# samtec_to_dsub.net
KiCad netlist of a schematic drawn in EAGLE
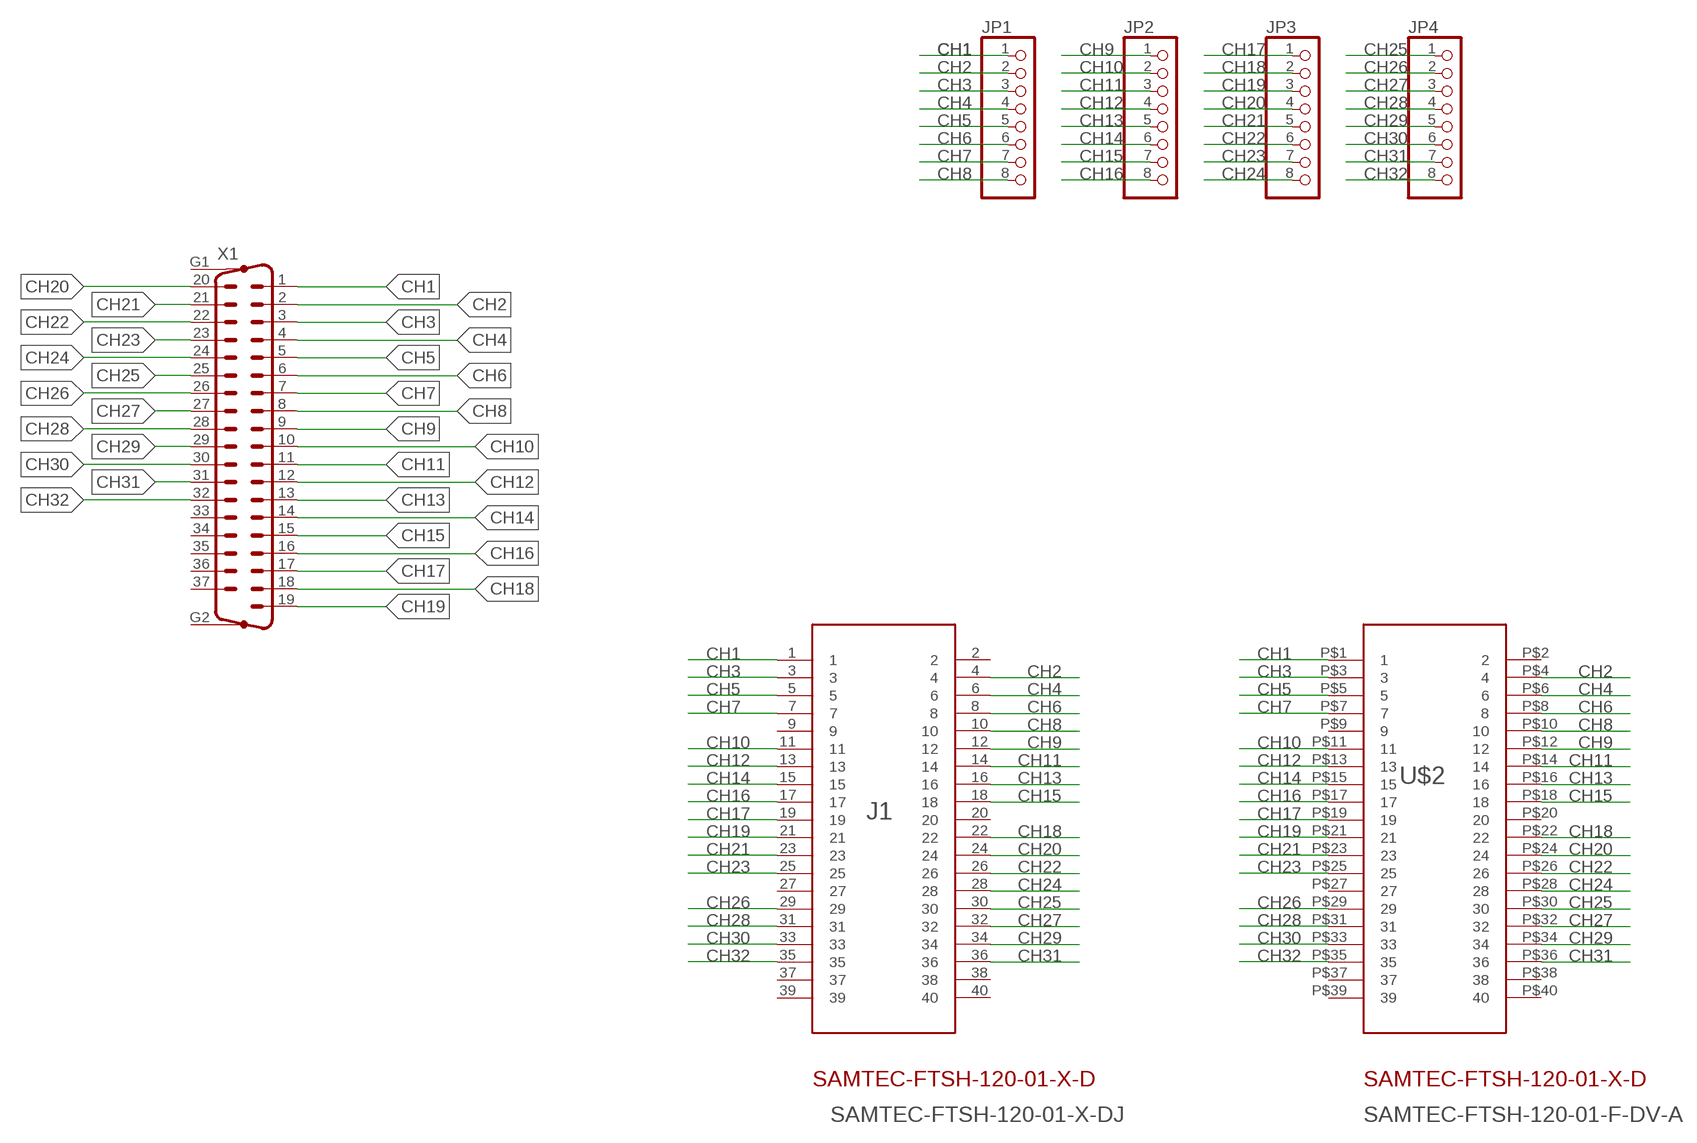
[diagram p0: schematic, sheet 1]

(export (version "E")
  (design (tool "Eeschema 10.0.6"))
  (components
    (comp (ref "J1")
      (value "SAMTEC-FTSH-120-01-X-DJ")
      (footprint "eagle-import:SAMTEC-FTSH-120-01-X-D")
      (libsource (lib "eagle-import") (part "SAMTEC-FTSH-120-01-X-DJ"))
    )
    (comp (ref "JP1")
      (value "PINHD-1X8")
      (footprint "eagle-import:1X08")
      (libsource (lib "eagle-import") (part "PINHD-1X8"))
    )
    (comp (ref "JP2")
      (value "PINHD-1X8")
      (footprint "eagle-import:1X08")
      (libsource (lib "eagle-import") (part "PINHD-1X8"))
    )
    (comp (ref "JP3")
      (value "PINHD-1X8")
      (footprint "eagle-import:1X08")
      (libsource (lib "eagle-import") (part "PINHD-1X8"))
    )
    (comp (ref "JP4")
      (value "PINHD-1X8")
      (footprint "eagle-import:1X08")
      (libsource (lib "eagle-import") (part "PINHD-1X8"))
    )
    (comp (ref "U$2")
      (value "SAMTEC-FTSH-120-01-F-DV-A")
      (footprint "eagle-import:SAMTEC-FTSH-LARGEPAD")
      (libsource (lib "eagle-import") (part "SAMTEC-FTSH-120-01-F-DV-A"))
    )
    (comp (ref "X1")
      (value "M37HP")
      (footprint "eagle-import:M37HP")
      (libsource (lib "eagle-import") (part "M37HP"))
    )
  )
  (nets
    (net (code "1") (name "CH1") (class "Default")
      (node (ref "J1") (pin "1") (pinfunction "1_1") (pintype "passive"))
      (node (ref "JP1") (pin "1") (pinfunction "1_1") (pintype "passive"))
      (node (ref "U$2") (pin "P$1") (pinfunction "1_P$1") (pintype "passive"))
      (node (ref "X1") (pin "1") (pinfunction "1_1") (pintype "passive"))
    )
    (net (code "2") (name "CH2") (class "Default")
      (node (ref "J1") (pin "4") (pinfunction "4_4") (pintype "passive"))
      (node (ref "JP1") (pin "2") (pinfunction "2_2") (pintype "passive"))
      (node (ref "U$2") (pin "P$4") (pinfunction "4_P$4") (pintype "passive"))
      (node (ref "X1") (pin "2") (pinfunction "2_2") (pintype "passive"))
    )
    (net (code "3") (name "CH3") (class "Default")
      (node (ref "J1") (pin "3") (pinfunction "3_3") (pintype "passive"))
      (node (ref "JP1") (pin "3") (pinfunction "3_3") (pintype "passive"))
      (node (ref "U$2") (pin "P$3") (pinfunction "3_P$3") (pintype "passive"))
      (node (ref "X1") (pin "3") (pinfunction "3_3") (pintype "passive"))
    )
    (net (code "4") (name "CH4") (class "Default")
      (node (ref "J1") (pin "6") (pinfunction "6_6") (pintype "passive"))
      (node (ref "JP1") (pin "4") (pinfunction "4_4") (pintype "passive"))
      (node (ref "U$2") (pin "P$6") (pinfunction "6_P$6") (pintype "passive"))
      (node (ref "X1") (pin "4") (pinfunction "4_4") (pintype "passive"))
    )
    (net (code "5") (name "CH5") (class "Default")
      (node (ref "J1") (pin "5") (pinfunction "5_5") (pintype "passive"))
      (node (ref "JP1") (pin "5") (pinfunction "5_5") (pintype "passive"))
      (node (ref "U$2") (pin "P$5") (pinfunction "5_P$5") (pintype "passive"))
      (node (ref "X1") (pin "5") (pinfunction "5_5") (pintype "passive"))
    )
    (net (code "6") (name "CH6") (class "Default")
      (node (ref "J1") (pin "8") (pinfunction "8_8") (pintype "passive"))
      (node (ref "JP1") (pin "6") (pinfunction "6_6") (pintype "passive"))
      (node (ref "U$2") (pin "P$8") (pinfunction "8_P$8") (pintype "passive"))
      (node (ref "X1") (pin "6") (pinfunction "6_6") (pintype "passive"))
    )
    (net (code "7") (name "CH7") (class "Default")
      (node (ref "J1") (pin "7") (pinfunction "7_7") (pintype "passive"))
      (node (ref "JP1") (pin "7") (pinfunction "7_7") (pintype "passive"))
      (node (ref "U$2") (pin "P$7") (pinfunction "7_P$7") (pintype "passive"))
      (node (ref "X1") (pin "7") (pinfunction "7_7") (pintype "passive"))
    )
    (net (code "8") (name "CH8") (class "Default")
      (node (ref "J1") (pin "10") (pinfunction "10_10") (pintype "passive"))
      (node (ref "JP1") (pin "8") (pinfunction "8_8") (pintype "passive"))
      (node (ref "U$2") (pin "P$10") (pinfunction "10_P$10") (pintype "passive"))
      (node (ref "X1") (pin "8") (pinfunction "8_8") (pintype "passive"))
    )
    (net (code "9") (name "CH9") (class "Default")
      (node (ref "J1") (pin "12") (pinfunction "12_12") (pintype "passive"))
      (node (ref "JP2") (pin "1") (pinfunction "1_1") (pintype "passive"))
      (node (ref "U$2") (pin "P$12") (pinfunction "12_P$12") (pintype "passive"))
      (node (ref "X1") (pin "9") (pinfunction "9_9") (pintype "passive"))
    )
    (net (code "10") (name "CH10") (class "Default")
      (node (ref "J1") (pin "11") (pinfunction "11_11") (pintype "passive"))
      (node (ref "JP2") (pin "2") (pinfunction "2_2") (pintype "passive"))
      (node (ref "U$2") (pin "P$11") (pinfunction "11_P$11") (pintype "passive"))
      (node (ref "X1") (pin "10") (pinfunction "10_10") (pintype "passive"))
    )
    (net (code "11") (name "CH11") (class "Default")
      (node (ref "J1") (pin "14") (pinfunction "14_14") (pintype "passive"))
      (node (ref "JP2") (pin "3") (pinfunction "3_3") (pintype "passive"))
      (node (ref "U$2") (pin "P$14") (pinfunction "14_P$14") (pintype "passive"))
      (node (ref "X1") (pin "11") (pinfunction "11_11") (pintype "passive"))
    )
    (net (code "12") (name "CH12") (class "Default")
      (node (ref "J1") (pin "13") (pinfunction "13_13") (pintype "passive"))
      (node (ref "JP2") (pin "4") (pinfunction "4_4") (pintype "passive"))
      (node (ref "U$2") (pin "P$13") (pinfunction "13_P$13") (pintype "passive"))
      (node (ref "X1") (pin "12") (pinfunction "12_12") (pintype "passive"))
    )
    (net (code "13") (name "CH13") (class "Default")
      (node (ref "J1") (pin "16") (pinfunction "16_16") (pintype "passive"))
      (node (ref "JP2") (pin "5") (pinfunction "5_5") (pintype "passive"))
      (node (ref "U$2") (pin "P$16") (pinfunction "16_P$16") (pintype "passive"))
      (node (ref "X1") (pin "13") (pinfunction "13_13") (pintype "passive"))
    )
    (net (code "14") (name "CH14") (class "Default")
      (node (ref "J1") (pin "15") (pinfunction "15_15") (pintype "passive"))
      (node (ref "JP2") (pin "6") (pinfunction "6_6") (pintype "passive"))
      (node (ref "U$2") (pin "P$15") (pinfunction "15_P$15") (pintype "passive"))
      (node (ref "X1") (pin "14") (pinfunction "14_14") (pintype "passive"))
    )
    (net (code "15") (name "CH15") (class "Default")
      (node (ref "J1") (pin "18") (pinfunction "18_18") (pintype "passive"))
      (node (ref "JP2") (pin "7") (pinfunction "7_7") (pintype "passive"))
      (node (ref "U$2") (pin "P$18") (pinfunction "18_P$18") (pintype "passive"))
      (node (ref "X1") (pin "15") (pinfunction "15_15") (pintype "passive"))
    )
    (net (code "16") (name "CH16") (class "Default")
      (node (ref "J1") (pin "17") (pinfunction "17_17") (pintype "passive"))
      (node (ref "JP2") (pin "8") (pinfunction "8_8") (pintype "passive"))
      (node (ref "U$2") (pin "P$17") (pinfunction "17_P$17") (pintype "passive"))
      (node (ref "X1") (pin "16") (pinfunction "16_16") (pintype "passive"))
    )
    (net (code "17") (name "CH17") (class "Default")
      (node (ref "J1") (pin "19") (pinfunction "19_19") (pintype "passive"))
      (node (ref "JP3") (pin "1") (pinfunction "1_1") (pintype "passive"))
      (node (ref "U$2") (pin "P$19") (pinfunction "19_P$19") (pintype "passive"))
      (node (ref "X1") (pin "17") (pinfunction "17_17") (pintype "passive"))
    )
    (net (code "18") (name "CH18") (class "Default")
      (node (ref "J1") (pin "22") (pinfunction "22_22") (pintype "passive"))
      (node (ref "JP3") (pin "2") (pinfunction "2_2") (pintype "passive"))
      (node (ref "U$2") (pin "P$22") (pinfunction "22_P$22") (pintype "passive"))
      (node (ref "X1") (pin "18") (pinfunction "18_18") (pintype "passive"))
    )
    (net (code "19") (name "CH19") (class "Default")
      (node (ref "J1") (pin "21") (pinfunction "21_21") (pintype "passive"))
      (node (ref "JP3") (pin "3") (pinfunction "3_3") (pintype "passive"))
      (node (ref "U$2") (pin "P$21") (pinfunction "21_P$21") (pintype "passive"))
      (node (ref "X1") (pin "19") (pinfunction "19_19") (pintype "passive"))
    )
    (net (code "20") (name "CH20") (class "Default")
      (node (ref "J1") (pin "24") (pinfunction "24_24") (pintype "passive"))
      (node (ref "JP3") (pin "4") (pinfunction "4_4") (pintype "passive"))
      (node (ref "U$2") (pin "P$24") (pinfunction "24_P$24") (pintype "passive"))
      (node (ref "X1") (pin "20") (pinfunction "20_20") (pintype "passive"))
    )
    (net (code "21") (name "CH21") (class "Default")
      (node (ref "J1") (pin "23") (pinfunction "23_23") (pintype "passive"))
      (node (ref "JP3") (pin "5") (pinfunction "5_5") (pintype "passive"))
      (node (ref "U$2") (pin "P$23") (pinfunction "23_P$23") (pintype "passive"))
      (node (ref "X1") (pin "21") (pinfunction "21_21") (pintype "passive"))
    )
    (net (code "22") (name "CH22") (class "Default")
      (node (ref "J1") (pin "26") (pinfunction "26_26") (pintype "passive"))
      (node (ref "JP3") (pin "6") (pinfunction "6_6") (pintype "passive"))
      (node (ref "U$2") (pin "P$26") (pinfunction "26_P$26") (pintype "passive"))
      (node (ref "X1") (pin "22") (pinfunction "22_22") (pintype "passive"))
    )
    (net (code "23") (name "CH23") (class "Default")
      (node (ref "J1") (pin "25") (pinfunction "25_25") (pintype "passive"))
      (node (ref "JP3") (pin "7") (pinfunction "7_7") (pintype "passive"))
      (node (ref "U$2") (pin "P$25") (pinfunction "25_P$25") (pintype "passive"))
      (node (ref "X1") (pin "23") (pinfunction "23_23") (pintype "passive"))
    )
    (net (code "24") (name "CH24") (class "Default")
      (node (ref "J1") (pin "28") (pinfunction "28_28") (pintype "passive"))
      (node (ref "JP3") (pin "8") (pinfunction "8_8") (pintype "passive"))
      (node (ref "U$2") (pin "P$28") (pinfunction "28_P$28") (pintype "passive"))
      (node (ref "X1") (pin "24") (pinfunction "24_24") (pintype "passive"))
    )
    (net (code "25") (name "CH25") (class "Default")
      (node (ref "J1") (pin "30") (pinfunction "30_30") (pintype "passive"))
      (node (ref "JP4") (pin "1") (pinfunction "1_1") (pintype "passive"))
      (node (ref "U$2") (pin "P$30") (pinfunction "30_P$30") (pintype "passive"))
      (node (ref "X1") (pin "25") (pinfunction "25_25") (pintype "passive"))
    )
    (net (code "26") (name "CH26") (class "Default")
      (node (ref "J1") (pin "29") (pinfunction "29_29") (pintype "passive"))
      (node (ref "JP4") (pin "2") (pinfunction "2_2") (pintype "passive"))
      (node (ref "U$2") (pin "P$29") (pinfunction "29_P$29") (pintype "passive"))
      (node (ref "X1") (pin "26") (pinfunction "26_26") (pintype "passive"))
    )
    (net (code "27") (name "CH27") (class "Default")
      (node (ref "J1") (pin "32") (pinfunction "32_32") (pintype "passive"))
      (node (ref "JP4") (pin "3") (pinfunction "3_3") (pintype "passive"))
      (node (ref "U$2") (pin "P$32") (pinfunction "32_P$32") (pintype "passive"))
      (node (ref "X1") (pin "27") (pinfunction "27_27") (pintype "passive"))
    )
    (net (code "28") (name "CH28") (class "Default")
      (node (ref "J1") (pin "31") (pinfunction "31_31") (pintype "passive"))
      (node (ref "JP4") (pin "4") (pinfunction "4_4") (pintype "passive"))
      (node (ref "U$2") (pin "P$31") (pinfunction "31_P$31") (pintype "passive"))
      (node (ref "X1") (pin "28") (pinfunction "28_28") (pintype "passive"))
    )
    (net (code "29") (name "CH29") (class "Default")
      (node (ref "J1") (pin "34") (pinfunction "34_34") (pintype "passive"))
      (node (ref "JP4") (pin "5") (pinfunction "5_5") (pintype "passive"))
      (node (ref "U$2") (pin "P$34") (pinfunction "34_P$34") (pintype "passive"))
      (node (ref "X1") (pin "29") (pinfunction "29_29") (pintype "passive"))
    )
    (net (code "30") (name "CH30") (class "Default")
      (node (ref "J1") (pin "33") (pinfunction "33_33") (pintype "passive"))
      (node (ref "JP4") (pin "6") (pinfunction "6_6") (pintype "passive"))
      (node (ref "U$2") (pin "P$33") (pinfunction "33_P$33") (pintype "passive"))
      (node (ref "X1") (pin "30") (pinfunction "30_30") (pintype "passive"))
    )
    (net (code "31") (name "CH31") (class "Default")
      (node (ref "J1") (pin "36") (pinfunction "36_36") (pintype "passive"))
      (node (ref "JP4") (pin "7") (pinfunction "7_7") (pintype "passive"))
      (node (ref "U$2") (pin "P$36") (pinfunction "36_P$36") (pintype "passive"))
      (node (ref "X1") (pin "31") (pinfunction "31_31") (pintype "passive"))
    )
    (net (code "32") (name "CH32") (class "Default")
      (node (ref "J1") (pin "35") (pinfunction "35_35") (pintype "passive"))
      (node (ref "JP4") (pin "8") (pinfunction "8_8") (pintype "passive"))
      (node (ref "U$2") (pin "P$35") (pinfunction "35_P$35") (pintype "passive"))
      (node (ref "X1") (pin "32") (pinfunction "32_32") (pintype "passive"))
    )
    (net (code "33") (name "unconnected-(J1-Pad2)") (class "Default")
      (node (ref "J1") (pin "2") (pinfunction "2_2") (pintype "passive"))
    )
    (net (code "34") (name "unconnected-(J1-Pad9)") (class "Default")
      (node (ref "J1") (pin "9") (pinfunction "9_9") (pintype "passive"))
    )
    (net (code "35") (name "unconnected-(J1-Pad20)") (class "Default")
      (node (ref "J1") (pin "20") (pinfunction "20_20") (pintype "passive"))
    )
    (net (code "36") (name "unconnected-(J1-Pad27)") (class "Default")
      (node (ref "J1") (pin "27") (pinfunction "27_27") (pintype "passive"))
    )
    (net (code "37") (name "unconnected-(J1-Pad37)") (class "Default")
      (node (ref "J1") (pin "37") (pinfunction "37_37") (pintype "passive"))
    )
    (net (code "38") (name "unconnected-(J1-Pad38)") (class "Default")
      (node (ref "J1") (pin "38") (pinfunction "38_38") (pintype "passive"))
    )
    (net (code "39") (name "unconnected-(J1-Pad39)") (class "Default")
      (node (ref "J1") (pin "39") (pinfunction "39_39") (pintype "passive"))
    )
    (net (code "40") (name "unconnected-(J1-Pad40)") (class "Default")
      (node (ref "J1") (pin "40") (pinfunction "40_40") (pintype "passive"))
    )
    (net (code "41") (name "unconnected-(U$2-2-PadP$2)") (class "Default")
      (node (ref "U$2") (pin "P$2") (pinfunction "2_P$2") (pintype "passive"))
    )
    (net (code "42") (name "unconnected-(U$2-9-PadP$9)") (class "Default")
      (node (ref "U$2") (pin "P$9") (pinfunction "9_P$9") (pintype "passive"))
    )
    (net (code "43") (name "unconnected-(U$2-20-PadP$20)") (class "Default")
      (node (ref "U$2") (pin "P$20") (pinfunction "20_P$20") (pintype "passive"))
    )
    (net (code "44") (name "unconnected-(U$2-27-PadP$27)") (class "Default")
      (node (ref "U$2") (pin "P$27") (pinfunction "27_P$27") (pintype "passive"))
    )
    (net (code "45") (name "unconnected-(U$2-37-PadP$37)") (class "Default")
      (node (ref "U$2") (pin "P$37") (pinfunction "37_P$37") (pintype "passive"))
    )
    (net (code "46") (name "unconnected-(U$2-38-PadP$38)") (class "Default")
      (node (ref "U$2") (pin "P$38") (pinfunction "38_P$38") (pintype "passive"))
    )
    (net (code "47") (name "unconnected-(U$2-39-PadP$39)") (class "Default")
      (node (ref "U$2") (pin "P$39") (pinfunction "39_P$39") (pintype "passive"))
    )
    (net (code "48") (name "unconnected-(U$2-40-PadP$40)") (class "Default")
      (node (ref "U$2") (pin "P$40") (pinfunction "40_P$40") (pintype "passive"))
    )
    (net (code "49") (name "unconnected-(X1-Pad33)") (class "Default")
      (node (ref "X1") (pin "33") (pinfunction "33_33") (pintype "passive"))
    )
    (net (code "50") (name "unconnected-(X1-Pad34)") (class "Default")
      (node (ref "X1") (pin "34") (pinfunction "34_34") (pintype "passive"))
    )
    (net (code "51") (name "unconnected-(X1-Pad35)") (class "Default")
      (node (ref "X1") (pin "35") (pinfunction "35_35") (pintype "passive"))
    )
    (net (code "52") (name "unconnected-(X1-Pad36)") (class "Default")
      (node (ref "X1") (pin "36") (pinfunction "36_36") (pintype "passive"))
    )
    (net (code "53") (name "unconnected-(X1-Pad37)") (class "Default")
      (node (ref "X1") (pin "37") (pinfunction "37_37") (pintype "passive"))
    )
    (net (code "54") (name "unconnected-(X1-PadG1)") (class "Default")
      (node (ref "X1") (pin "G1") (pinfunction "G1_G1") (pintype "passive"))
    )
    (net (code "55") (name "unconnected-(X1-PadG2)") (class "Default")
      (node (ref "X1") (pin "G2") (pinfunction "G2_G2") (pintype "passive"))
    )
  )
)
